# Ethernet.net
KiCad netlist of a schematic drawn in Altium Designer
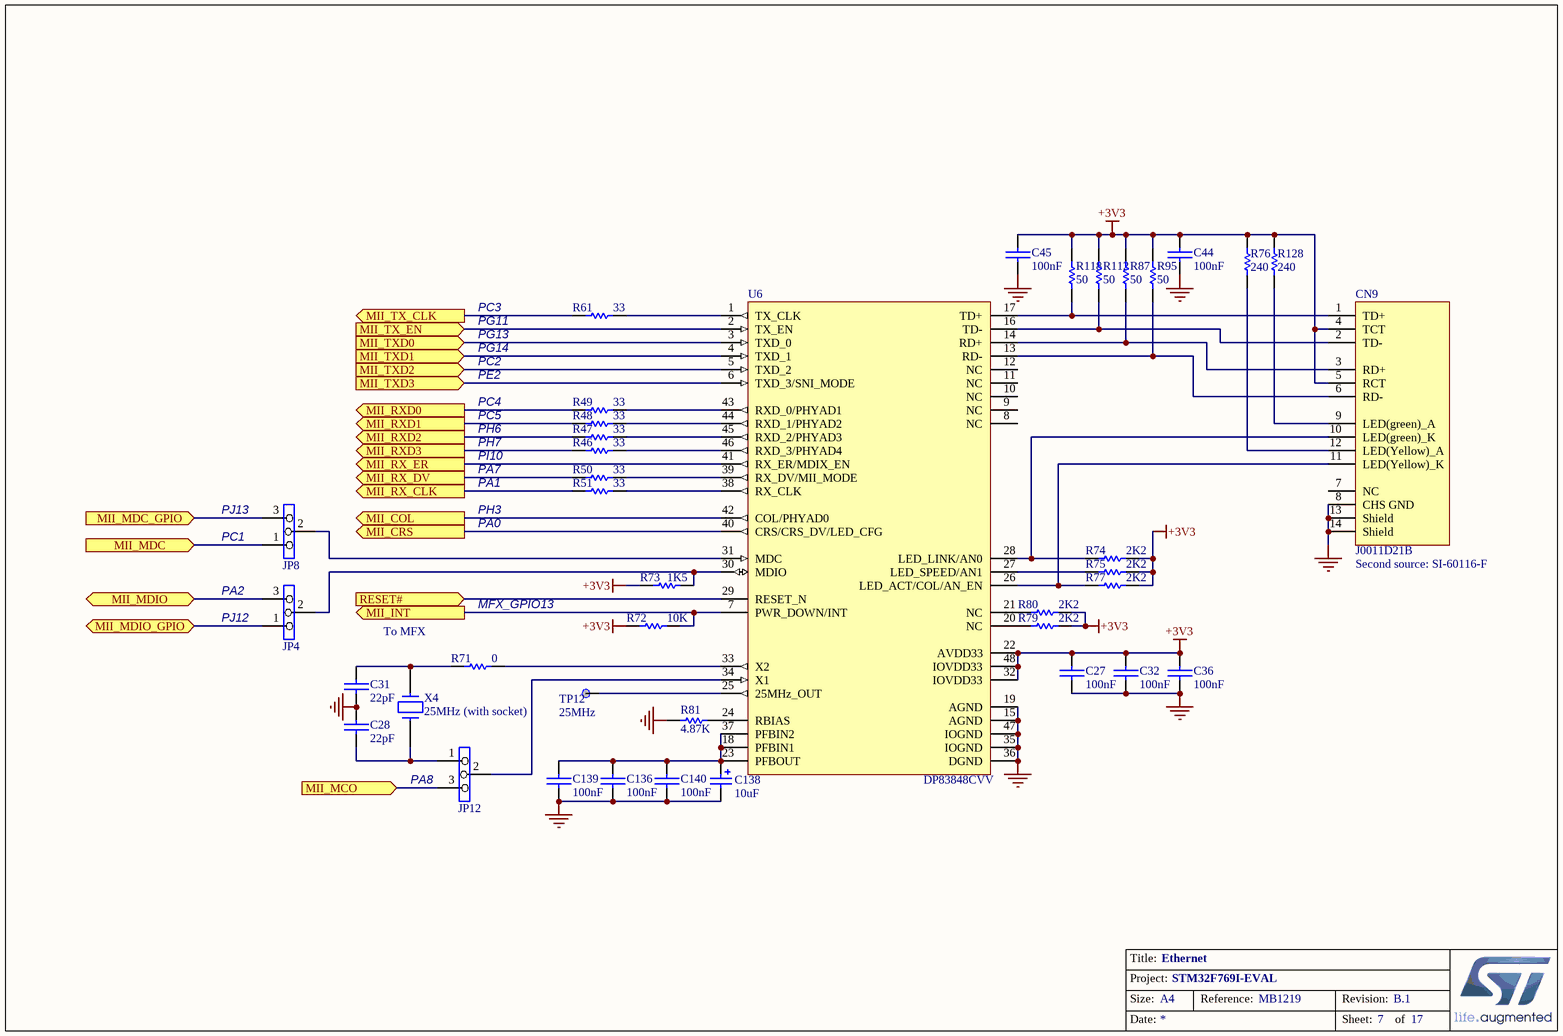
[diagram p0: Ethernet.SchDoc]

(export (version "E")
  (design (tool "Eeschema 10.0.6"))
  (components
    (comp (ref "C27")
      (value "100nF")
      (footprint "0603C")
      (description "Capacitor")
      (libsource (lib "*") (part "CAP"))
    )
    (comp (ref "C28")
      (value "22pF")
      (footprint "0603C")
      (description "Capacitor")
      (libsource (lib "*") (part "CAP"))
    )
    (comp (ref "C31")
      (value "22pF")
      (footprint "0603C")
      (description "Capacitor")
      (libsource (lib "*") (part "CAP"))
    )
    (comp (ref "C32")
      (value "100nF")
      (footprint "0603C")
      (description "Capacitor")
      (libsource (lib "*") (part "CAP"))
    )
    (comp (ref "C36")
      (value "100nF")
      (footprint "0603C")
      (description "Capacitor")
      (libsource (lib "*") (part "CAP"))
    )
    (comp (ref "C44")
      (value "100nF")
      (footprint "0603C")
      (description "Capacitor")
      (libsource (lib "*") (part "CAP"))
    )
    (comp (ref "C45")
      (value "100nF")
      (footprint "0603C")
      (description "Capacitor")
      (libsource (lib "*") (part "CAP"))
    )
    (comp (ref "C136")
      (value "100nF")
      (footprint "0603C")
      (description "Capacitor")
      (libsource (lib "*") (part "CAP"))
    )
    (comp (ref "C138")
      (value "10uF")
      (footprint "TAN-A")
      (description "Polarized Capacitor (Radial)")
      (fields (field (name "PUBLISHER") "Altium Limited"))
      (libsource (lib "Miscellaneous Devices") (part "Cap Pol1"))
    )
    (comp (ref "C139")
      (value "100nF")
      (footprint "0603C")
      (description "Capacitor")
      (libsource (lib "*") (part "CAP"))
    )
    (comp (ref "C140")
      (value "100nF")
      (footprint "0603C")
      (description "Capacitor")
      (libsource (lib "*") (part "CAP"))
    )
    (comp (ref "CN9")
      (value "J0011D21B")
      (footprint "RJ45_J0011D01BNL")
      (libsource (lib "MB784") (part "J0011D21B"))
    )
    (comp (ref "JP4") (value "~") (footprint "SIP3") (libsource (lib "STR910_SCHLIB") (part "Jumper3")))
    (comp (ref "JP8") (value "~") (footprint "SIP3") (libsource (lib "STR910_SCHLIB") (part "Jumper3")))
    (comp (ref "JP12") (value "~") (footprint "SIP3") (libsource (lib "STR910_SCHLIB") (part "Jumper3")))
    (comp (ref "R46")
      (value "33")
      (footprint "0603R")
      (description "Resistor")
      (fields (field (name "PUBLISHER") "Altium Limited"))
      (libsource (lib "Miscellaneous Devices") (part "Res1"))
    )
    (comp (ref "R47")
      (value "33")
      (footprint "0603R")
      (description "Resistor")
      (fields (field (name "PUBLISHER") "Altium Limited"))
      (libsource (lib "Miscellaneous Devices") (part "Res1"))
    )
    (comp (ref "R48")
      (value "33")
      (footprint "0603R")
      (description "Resistor")
      (fields (field (name "PUBLISHER") "Altium Limited"))
      (libsource (lib "Miscellaneous Devices") (part "Res1"))
    )
    (comp (ref "R49")
      (value "33")
      (footprint "0603R")
      (description "Resistor")
      (fields (field (name "PUBLISHER") "Altium Limited"))
      (libsource (lib "Miscellaneous Devices") (part "Res1"))
    )
    (comp (ref "R50")
      (value "33")
      (footprint "0603R")
      (description "Resistor")
      (fields (field (name "PUBLISHER") "Altium Limited"))
      (libsource (lib "Miscellaneous Devices") (part "Res1"))
    )
    (comp (ref "R51")
      (value "33")
      (footprint "0603R")
      (description "Resistor")
      (fields (field (name "PUBLISHER") "Altium Limited"))
      (libsource (lib "Miscellaneous Devices") (part "Res1"))
    )
    (comp (ref "R61")
      (value "33")
      (footprint "0603R")
      (description "Resistor")
      (fields (field (name "PUBLISHER") "Altium Limited"))
      (libsource (lib "Miscellaneous Devices") (part "Res1"))
    )
    (comp (ref "R71")
      (value "0")
      (footprint "0603R")
      (description "Resistor")
      (fields (field (name "PUBLISHER") "Altium Limited"))
      (libsource (lib "Miscellaneous Devices") (part "Res1"))
    )
    (comp (ref "R72")
      (value "10K")
      (footprint "0603R")
      (description "Resistor")
      (fields (field (name "PUBLISHER") "Altium Limited"))
      (libsource (lib "Miscellaneous Devices") (part "Res1"))
    )
    (comp (ref "R73")
      (value "1K5")
      (footprint "0603R")
      (description "Resistor")
      (fields (field (name "PUBLISHER") "Altium Limited"))
      (libsource (lib "Miscellaneous Devices") (part "Res1"))
    )
    (comp (ref "R74")
      (value "2K2")
      (footprint "0603R")
      (description "Resistor")
      (fields (field (name "PUBLISHER") "Altium Limited"))
      (libsource (lib "Miscellaneous Devices") (part "Res1"))
    )
    (comp (ref "R75")
      (value "2K2")
      (footprint "0603R")
      (description "Resistor")
      (fields (field (name "PUBLISHER") "Altium Limited"))
      (libsource (lib "Miscellaneous Devices") (part "Res1"))
    )
    (comp (ref "R76")
      (value "240")
      (footprint "0603R")
      (description "Resistor")
      (fields (field (name "PUBLISHER") "Altium Limited"))
      (libsource (lib "Miscellaneous Devices") (part "Res1"))
    )
    (comp (ref "R77")
      (value "2K2")
      (footprint "0603R")
      (description "Resistor")
      (fields (field (name "PUBLISHER") "Altium Limited"))
      (libsource (lib "Miscellaneous Devices") (part "Res1"))
    )
    (comp (ref "R79")
      (value "2K2")
      (footprint "0603R")
      (description "Resistor")
      (fields (field (name "PUBLISHER") "Altium Limited"))
      (libsource (lib "Miscellaneous Devices") (part "Res1"))
    )
    (comp (ref "R80")
      (value "2K2")
      (footprint "0603R")
      (description "Resistor")
      (fields (field (name "PUBLISHER") "Altium Limited"))
      (libsource (lib "Miscellaneous Devices") (part "Res1"))
    )
    (comp (ref "R81")
      (value "4.87K")
      (footprint "0603R")
      (description "Resistor")
      (fields (field (name "PUBLISHER") "Altium Limited"))
      (libsource (lib "Miscellaneous Devices") (part "Res1"))
    )
    (comp (ref "R87")
      (value "50")
      (footprint "0603R")
      (description "Resistor")
      (fields (field (name "PUBLISHER") "Altium Limited"))
      (libsource (lib "Miscellaneous Devices") (part "Res1"))
    )
    (comp (ref "R95")
      (value "50")
      (footprint "0603R")
      (description "Resistor")
      (fields (field (name "PUBLISHER") "Altium Limited"))
      (libsource (lib "Miscellaneous Devices") (part "Res1"))
    )
    (comp (ref "R112")
      (value "50")
      (footprint "0603R")
      (description "Resistor")
      (fields (field (name "PUBLISHER") "Altium Limited"))
      (libsource (lib "Miscellaneous Devices") (part "Res1"))
    )
    (comp (ref "R118")
      (value "50")
      (footprint "0603R")
      (description "Resistor")
      (fields (field (name "PUBLISHER") "Altium Limited"))
      (libsource (lib "Miscellaneous Devices") (part "Res1"))
    )
    (comp (ref "R128")
      (value "240")
      (footprint "0603R")
      (description "Resistor")
      (fields (field (name "PUBLISHER") "Altium Limited"))
      (libsource (lib "Miscellaneous Devices") (part "Res1"))
    )
    (comp (ref "TP12") (value "25MHz") (footprint "TP") (libsource (lib "*") (part "TP")))
    (comp (ref "U6")
      (value "DP83848CVV")
      (footprint "LQFP48_0R5_9X9")
      (libsource (lib "MB784") (part "DP83848CVV"))
    )
    (comp (ref "X4")
      (value "25MHz (with socket)")
      (footprint "XTAL_socket")
      (description "Crystal")
      (libsource (lib "*") (part "CRYSTAL"))
    )
  )
  (nets
    (net (code "1") (name "+3V3") (class "Default")
      (node (ref "C27") (pin "1") (pinfunction "1_1") (pintype "passive"))
      (node (ref "C32") (pin "2") (pinfunction "2_2") (pintype "passive"))
      (node (ref "C36") (pin "2") (pinfunction "2_2") (pintype "passive"))
      (node (ref "C44") (pin "2") (pinfunction "2_2") (pintype "passive"))
      (node (ref "C45") (pin "2") (pinfunction "2_2") (pintype "passive"))
      (node (ref "CN9") (pin "4") (pinfunction "TCT_4") (pintype "passive"))
      (node (ref "CN9") (pin "5") (pinfunction "RCT_5") (pintype "passive"))
      (node (ref "R112") (pin "1") (pinfunction "1_1") (pintype "passive"))
      (node (ref "R118") (pin "1") (pinfunction "1_1") (pintype "passive"))
      (node (ref "R128") (pin "2") (pinfunction "2_2") (pintype "passive"))
      (node (ref "R72") (pin "1") (pinfunction "1_1") (pintype "passive"))
      (node (ref "R73") (pin "2") (pinfunction "2_2") (pintype "passive"))
      (node (ref "R74") (pin "2") (pinfunction "2_2") (pintype "passive"))
      (node (ref "R75") (pin "2") (pinfunction "2_2") (pintype "passive"))
      (node (ref "R76") (pin "2") (pinfunction "2_2") (pintype "passive"))
      (node (ref "R77") (pin "2") (pinfunction "2_2") (pintype "passive"))
      (node (ref "R79") (pin "2") (pinfunction "2_2") (pintype "passive"))
      (node (ref "R80") (pin "2") (pinfunction "2_2") (pintype "passive"))
      (node (ref "R87") (pin "1") (pinfunction "1_1") (pintype "passive"))
      (node (ref "R95") (pin "1") (pinfunction "1_1") (pintype "passive"))
      (node (ref "U6") (pin "22") (pinfunction "AVDD33_22") (pintype "passive"))
      (node (ref "U6") (pin "32") (pinfunction "IOVDD33_32") (pintype "passive"))
      (node (ref "U6") (pin "48") (pinfunction "IOVDD33_48") (pintype "passive"))
    )
    (net (code "2") (name "/MII_COL") (class "Default")
      (node (ref "U6") (pin "42") (pinfunction "COL/PHYAD0_42") (pintype "output"))
    )
    (net (code "3") (name "/MII_CRS") (class "Default")
      (node (ref "U6") (pin "40") (pinfunction "CRS/CRS_DV/LED_CFG_40") (pintype "output"))
    )
    (net (code "4") (name "/MII_INT") (class "Default")
      (node (ref "R72") (pin "2") (pinfunction "2_2") (pintype "passive"))
      (node (ref "U6") (pin "7") (pinfunction "PWR_DOWN/INT_7") (pintype "passive"))
    )
    (net (code "5") (name "/MII_MCO") (class "Default") (node (ref "JP12") (pin "3") (pintype "passive")))
    (net (code "6") (name "/MII_MDC") (class "Default") (node (ref "JP8") (pin "1") (pintype "passive")))
    (net (code "7") (name "/MII_MDC_GPIO") (class "Default") (node (ref "JP8") (pin "3") (pintype "passive")))
    (net (code "8") (name "/MII_MDIO") (class "Default") (node (ref "JP4") (pin "3") (pintype "passive")))
    (net (code "9") (name "/MII_MDIO_GPIO") (class "Default")
      (node (ref "JP4") (pin "1") (pintype "passive"))
    )
    (net (code "10") (name "/MII_RXD0") (class "Default")
      (node (ref "R49") (pin "2") (pinfunction "2_2") (pintype "passive"))
    )
    (net (code "11") (name "/MII_RXD1") (class "Default")
      (node (ref "R48") (pin "2") (pinfunction "2_2") (pintype "passive"))
    )
    (net (code "12") (name "/MII_RXD2") (class "Default")
      (node (ref "R47") (pin "2") (pinfunction "2_2") (pintype "passive"))
    )
    (net (code "13") (name "/MII_RXD3") (class "Default")
      (node (ref "R46") (pin "2") (pinfunction "2_2") (pintype "passive"))
    )
    (net (code "14") (name "/MII_RX_CLK") (class "Default")
      (node (ref "R51") (pin "2") (pinfunction "2_2") (pintype "passive"))
    )
    (net (code "15") (name "/MII_RX_DV") (class "Default")
      (node (ref "R50") (pin "2") (pinfunction "2_2") (pintype "passive"))
    )
    (net (code "16") (name "/MII_RX_ER") (class "Default")
      (node (ref "U6") (pin "41") (pinfunction "RX_ER/MDIX_EN_41") (pintype "output"))
    )
    (net (code "17") (name "/MII_TXD0") (class "Default")
      (node (ref "U6") (pin "3") (pinfunction "TXD_0_3") (pintype "input"))
    )
    (net (code "18") (name "/MII_TXD1") (class "Default")
      (node (ref "U6") (pin "4") (pinfunction "TXD_1_4") (pintype "input"))
    )
    (net (code "19") (name "/MII_TXD2") (class "Default")
      (node (ref "U6") (pin "5") (pinfunction "TXD_2_5") (pintype "input"))
    )
    (net (code "20") (name "/MII_TXD3") (class "Default")
      (node (ref "U6") (pin "6") (pinfunction "TXD_3/SNI_MODE_6") (pintype "input"))
    )
    (net (code "21") (name "/MII_TX_CLK") (class "Default")
      (node (ref "R61") (pin "2") (pinfunction "2_2") (pintype "passive"))
    )
    (net (code "22") (name "/MII_TX_EN") (class "Default")
      (node (ref "U6") (pin "2") (pinfunction "TX_EN_2") (pintype "input"))
    )
    (net (code "23") (name "/RESET#") (class "Default")
      (node (ref "U6") (pin "29") (pinfunction "RESET_N_29") (pintype "passive"))
    )
    (net (code "24") (name "GND") (class "Default")
      (node (ref "C136") (pin "1") (pinfunction "1_1") (pintype "passive"))
      (node (ref "C138") (pin "2") (pinfunction "2_2") (pintype "passive"))
      (node (ref "C139") (pin "2") (pinfunction "2_2") (pintype "passive"))
      (node (ref "C140") (pin "1") (pinfunction "1_1") (pintype "passive"))
      (node (ref "C27") (pin "2") (pinfunction "2_2") (pintype "passive"))
      (node (ref "C28") (pin "2") (pinfunction "2_2") (pintype "passive"))
      (node (ref "C31") (pin "1") (pinfunction "1_1") (pintype "passive"))
      (node (ref "C32") (pin "1") (pinfunction "1_1") (pintype "passive"))
      (node (ref "C36") (pin "1") (pinfunction "1_1") (pintype "passive"))
      (node (ref "C44") (pin "1") (pinfunction "1_1") (pintype "passive"))
      (node (ref "C45") (pin "1") (pinfunction "1_1") (pintype "passive"))
      (node (ref "CN9") (pin "13") (pinfunction "Shield_13") (pintype "passive"))
      (node (ref "CN9") (pin "14") (pinfunction "Shield_14") (pintype "passive"))
      (node (ref "CN9") (pin "8") (pinfunction "CHS_GND_8") (pintype "passive"))
      (node (ref "R81") (pin "1") (pinfunction "1_1") (pintype "passive"))
      (node (ref "U6") (pin "15") (pinfunction "AGND_15") (pintype "passive"))
      (node (ref "U6") (pin "19") (pinfunction "AGND_19") (pintype "passive"))
      (node (ref "U6") (pin "35") (pinfunction "IOGND_35") (pintype "passive"))
      (node (ref "U6") (pin "36") (pinfunction "DGND_36") (pintype "passive"))
      (node (ref "U6") (pin "47") (pinfunction "IOGND_47") (pintype "passive"))
    )
    (net (code "25") (name "Net-(C28-Pad1)") (class "Default")
      (node (ref "C28") (pin "1") (pinfunction "1_1") (pintype "passive"))
      (node (ref "JP12") (pin "1") (pintype "passive"))
      (node (ref "X4") (pin "1") (pinfunction "1_1") (pintype "passive"))
    )
    (net (code "26") (name "Net-(C31-Pad2)") (class "Default")
      (node (ref "C31") (pin "2") (pinfunction "2_2") (pintype "passive"))
      (node (ref "R71") (pin "2") (pinfunction "2_2") (pintype "passive"))
      (node (ref "X4") (pin "2") (pinfunction "2_2") (pintype "passive"))
    )
    (net (code "27") (name "Net-(CN9-LED(Yellow)_A)") (class "Default")
      (node (ref "CN9") (pin "12") (pinfunction "LED(Yellow)_A_12") (pintype "passive"))
      (node (ref "R76") (pin "1") (pinfunction "1_1") (pintype "passive"))
    )
    (net (code "28") (name "Net-(CN9-LED(Yellow)_K)") (class "Default")
      (node (ref "CN9") (pin "11") (pinfunction "LED(Yellow)_K_11") (pintype "passive"))
      (node (ref "R77") (pin "1") (pinfunction "1_1") (pintype "passive"))
      (node (ref "U6") (pin "26") (pinfunction "LED_ACT/COL/AN_EN_26") (pintype "passive"))
    )
    (net (code "29") (name "Net-(CN9-LED(green)_A)") (class "Default")
      (node (ref "CN9") (pin "9") (pinfunction "LED(green)_A_9") (pintype "passive"))
      (node (ref "R128") (pin "1") (pinfunction "1_1") (pintype "passive"))
    )
    (net (code "30") (name "Net-(CN9-LED(green)_K)") (class "Default")
      (node (ref "CN9") (pin "10") (pinfunction "LED(green)_K_10") (pintype "passive"))
      (node (ref "R74") (pin "1") (pinfunction "1_1") (pintype "passive"))
      (node (ref "U6") (pin "28") (pinfunction "LED_LINK/AN0_28") (pintype "passive"))
    )
    (net (code "31") (name "Net-(CN9-RD+)") (class "Default")
      (node (ref "CN9") (pin "3") (pinfunction "RD+_3") (pintype "passive"))
      (node (ref "R87") (pin "2") (pinfunction "2_2") (pintype "passive"))
      (node (ref "U6") (pin "14") (pinfunction "RD+_14") (pintype "passive"))
    )
    (net (code "32") (name "Net-(CN9-RD-)") (class "Default")
      (node (ref "CN9") (pin "6") (pinfunction "RD-_6") (pintype "passive"))
      (node (ref "R95") (pin "2") (pinfunction "2_2") (pintype "passive"))
      (node (ref "U6") (pin "13") (pinfunction "RD-_13") (pintype "passive"))
    )
    (net (code "33") (name "Net-(CN9-TD+)") (class "Default")
      (node (ref "CN9") (pin "1") (pinfunction "TD+_1") (pintype "passive"))
      (node (ref "R118") (pin "2") (pinfunction "2_2") (pintype "passive"))
      (node (ref "U6") (pin "17") (pinfunction "TD+_17") (pintype "passive"))
    )
    (net (code "34") (name "Net-(CN9-TD-)") (class "Default")
      (node (ref "CN9") (pin "2") (pinfunction "TD-_2") (pintype "passive"))
      (node (ref "R112") (pin "2") (pinfunction "2_2") (pintype "passive"))
      (node (ref "U6") (pin "16") (pinfunction "TD-_16") (pintype "passive"))
    )
    (net (code "35") (name "Net-(R79-Pad1)") (class "Default")
      (node (ref "R79") (pin "1") (pinfunction "1_1") (pintype "passive"))
      (node (ref "U6") (pin "20") (pinfunction "NC_20") (pintype "passive"))
    )
    (net (code "36") (name "Net-(R80-Pad1)") (class "Default")
      (node (ref "R80") (pin "1") (pinfunction "1_1") (pintype "passive"))
      (node (ref "U6") (pin "21") (pinfunction "NC_21") (pintype "passive"))
    )
    (net (code "37") (name "Net-(U6-25MHz_OUT)") (class "Default")
      (node (ref "TP12") (pin "1") (pinfunction "1_1") (pintype "passive"))
      (node (ref "U6") (pin "25") (pinfunction "25MHz_OUT_25") (pintype "output"))
    )
    (net (code "38") (name "Net-(U6-LED_SPEED{slash}AN1)") (class "Default")
      (node (ref "R75") (pin "1") (pinfunction "1_1") (pintype "passive"))
      (node (ref "U6") (pin "27") (pinfunction "LED_SPEED/AN1_27") (pintype "passive"))
    )
    (net (code "39") (name "Net-(U6-MDC)") (class "Default")
      (node (ref "JP8") (pin "2") (pintype "passive"))
      (node (ref "U6") (pin "31") (pinfunction "MDC_31") (pintype "input"))
    )
    (net (code "40") (name "Net-(U6-MDIO)") (class "Default")
      (node (ref "JP4") (pin "2") (pintype "passive"))
      (node (ref "R73") (pin "1") (pinfunction "1_1") (pintype "passive"))
      (node (ref "U6") (pin "30") (pinfunction "MDIO_30") (pintype "bidirectional"))
    )
    (net (code "41") (name "Net-(U6-PFBIN1)") (class "Default")
      (node (ref "C136") (pin "2") (pinfunction "2_2") (pintype "passive"))
      (node (ref "C138") (pin "1") (pinfunction "1_1") (pintype "passive"))
      (node (ref "C139") (pin "1") (pinfunction "1_1") (pintype "passive"))
      (node (ref "C140") (pin "2") (pinfunction "2_2") (pintype "passive"))
      (node (ref "U6") (pin "18") (pinfunction "PFBIN1_18") (pintype "passive"))
      (node (ref "U6") (pin "23") (pinfunction "PFBOUT_23") (pintype "passive"))
      (node (ref "U6") (pin "37") (pinfunction "PFBIN2_37") (pintype "passive"))
    )
    (net (code "42") (name "Net-(U6-RBIAS)") (class "Default")
      (node (ref "R81") (pin "2") (pinfunction "2_2") (pintype "passive"))
      (node (ref "U6") (pin "24") (pinfunction "RBIAS_24") (pintype "passive"))
    )
    (net (code "43") (name "Net-(U6-RXD_0{slash}PHYAD1)") (class "Default")
      (node (ref "R49") (pin "1") (pinfunction "1_1") (pintype "passive"))
      (node (ref "U6") (pin "43") (pinfunction "RXD_0/PHYAD1_43") (pintype "output"))
    )
    (net (code "44") (name "Net-(U6-RXD_1{slash}PHYAD2)") (class "Default")
      (node (ref "R48") (pin "1") (pinfunction "1_1") (pintype "passive"))
      (node (ref "U6") (pin "44") (pinfunction "RXD_1/PHYAD2_44") (pintype "output"))
    )
    (net (code "45") (name "Net-(U6-RXD_2{slash}PHYAD3)") (class "Default")
      (node (ref "R47") (pin "1") (pinfunction "1_1") (pintype "passive"))
      (node (ref "U6") (pin "45") (pinfunction "RXD_2/PHYAD3_45") (pintype "output"))
    )
    (net (code "46") (name "Net-(U6-RXD_3{slash}PHYAD4)") (class "Default")
      (node (ref "R46") (pin "1") (pinfunction "1_1") (pintype "passive"))
      (node (ref "U6") (pin "46") (pinfunction "RXD_3/PHYAD4_46") (pintype "output"))
    )
    (net (code "47") (name "Net-(U6-RX_CLK)") (class "Default")
      (node (ref "R51") (pin "1") (pinfunction "1_1") (pintype "passive"))
      (node (ref "U6") (pin "38") (pinfunction "RX_CLK_38") (pintype "output"))
    )
    (net (code "48") (name "Net-(U6-RX_DV{slash}MII_MODE)") (class "Default")
      (node (ref "R50") (pin "1") (pinfunction "1_1") (pintype "passive"))
      (node (ref "U6") (pin "39") (pinfunction "RX_DV/MII_MODE_39") (pintype "output"))
    )
    (net (code "49") (name "Net-(U6-TX_CLK)") (class "Default")
      (node (ref "R61") (pin "1") (pinfunction "1_1") (pintype "passive"))
      (node (ref "U6") (pin "1") (pinfunction "TX_CLK_1") (pintype "output"))
    )
    (net (code "50") (name "Net-(U6-X1)") (class "Default")
      (node (ref "JP12") (pin "2") (pintype "passive"))
      (node (ref "U6") (pin "34") (pinfunction "X1_34") (pintype "input"))
    )
    (net (code "51") (name "Net-(U6-X2)") (class "Default")
      (node (ref "R71") (pin "1") (pinfunction "1_1") (pintype "passive"))
      (node (ref "U6") (pin "33") (pinfunction "X2_33") (pintype "output"))
    )
    (net (code "52") (name "unconnected-(CN9-NC-Pad7)") (class "Default")
      (node (ref "CN9") (pin "7") (pinfunction "NC_7") (pintype "passive"))
    )
    (net (code "53") (name "unconnected-(U6-NC-Pad8)") (class "Default")
      (node (ref "U6") (pin "8") (pinfunction "NC_8") (pintype "passive"))
    )
    (net (code "54") (name "unconnected-(U6-NC-Pad9)") (class "Default")
      (node (ref "U6") (pin "9") (pinfunction "NC_9") (pintype "passive"))
    )
    (net (code "55") (name "unconnected-(U6-NC-Pad10)") (class "Default")
      (node (ref "U6") (pin "10") (pinfunction "NC_10") (pintype "passive"))
    )
    (net (code "56") (name "unconnected-(U6-NC-Pad11)") (class "Default")
      (node (ref "U6") (pin "11") (pinfunction "NC_11") (pintype "passive"))
    )
    (net (code "57") (name "unconnected-(U6-NC-Pad12)") (class "Default")
      (node (ref "U6") (pin "12") (pinfunction "NC_12") (pintype "passive"))
    )
  )
)
